# Bare_Arduino.net
KiCad netlist of a schematic drawn in EAGLE
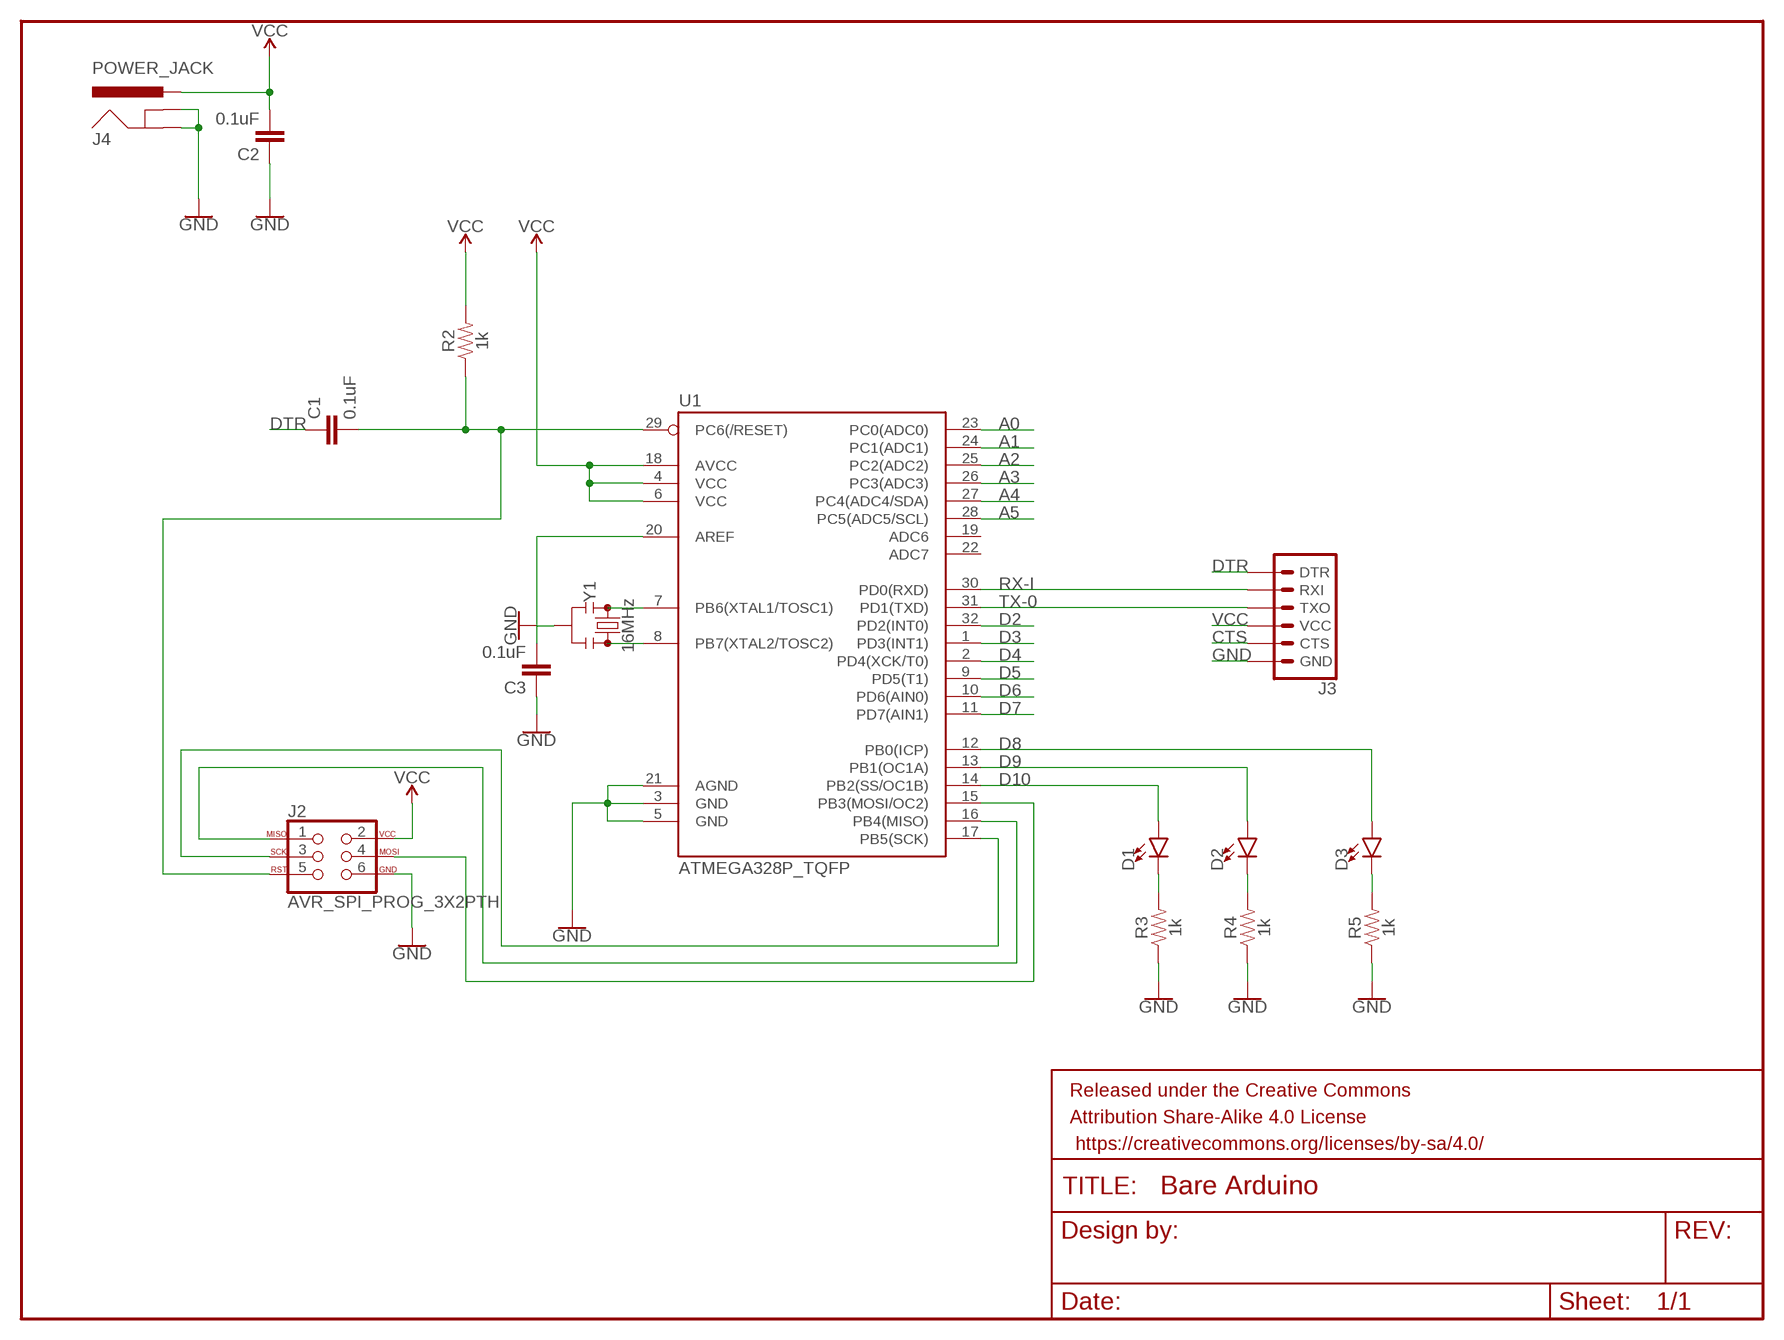
[diagram p0: schematic, sheet 1]

(export (version "E")
  (design (tool "Eeschema 10.0.6"))
  (components
    (comp (ref "C1")
      (value "0.1uF")
      (footprint "eagle-import:CAP-PTH-SMALL-KIT")
      (libsource (lib "eagle-import") (part "0.1UF-KIT-EZ-50V-20%"))
    )
    (comp (ref "C2")
      (value "0.1uF")
      (footprint "eagle-import:CAP-PTH-SMALL-KIT")
      (libsource (lib "eagle-import") (part "0.1UF-KIT-EZ-50V-20%"))
    )
    (comp (ref "C3")
      (value "0.1uF")
      (footprint "eagle-import:CAP-PTH-SMALL-KIT")
      (libsource (lib "eagle-import") (part "0.1UF-KIT-EZ-50V-20%"))
    )
    (comp (ref "D1")
      (value "LED5MM")
      (footprint "eagle-import:LED_5MM")
      (libsource (lib "eagle-import") (part "LED5MM"))
    )
    (comp (ref "D2")
      (value "LED5MM")
      (footprint "eagle-import:LED_5MM")
      (libsource (lib "eagle-import") (part "LED5MM"))
    )
    (comp (ref "D3")
      (value "LED5MM")
      (footprint "eagle-import:LED_5MM")
      (libsource (lib "eagle-import") (part "LED5MM"))
    )
    (comp (ref "FRAME1")
      (value "FRAME-LETTER")
      (footprint "eagle-import:CREATIVE_COMMONS")
      (libsource (lib "eagle-import") (part "FRAME-LETTER"))
    )
    (comp (ref "J2")
      (value "AVR_SPI_PROG_3X2PTH")
      (footprint "eagle-import:2X3")
      (libsource (lib "eagle-import") (part "AVR_SPI_PROG_3X2PTH"))
    )
    (comp (ref "J3")
      (value "6_PIN_SERIAL_TARGET")
      (footprint "eagle-import:1X06")
      (libsource (lib "eagle-import") (part "6_PIN_SERIAL_TARGET"))
    )
    (comp (ref "J4")
      (value "POWER_JACK")
      (footprint "eagle-import:POWER_JACK_PTH")
      (libsource (lib "eagle-import") (part "POWER_JACK"))
    )
    (comp (ref "R2")
      (value "1k")
      (footprint "eagle-import:AXIAL-0.3-KIT")
      (libsource (lib "eagle-import") (part "RESISTORAXIAL-0.3-KIT"))
    )
    (comp (ref "R3")
      (value "1k")
      (footprint "eagle-import:AXIAL-0.3-KIT")
      (libsource (lib "eagle-import") (part "RESISTORAXIAL-0.3-KIT"))
    )
    (comp (ref "R4")
      (value "1k")
      (footprint "eagle-import:AXIAL-0.3-KIT")
      (libsource (lib "eagle-import") (part "RESISTORAXIAL-0.3-KIT"))
    )
    (comp (ref "R5")
      (value "1k")
      (footprint "eagle-import:AXIAL-0.3-KIT")
      (libsource (lib "eagle-import") (part "RESISTORAXIAL-0.3-KIT"))
    )
    (comp (ref "U1")
      (value "ATMEGA328P_TQFP")
      (footprint "eagle-import:TQFP32-08")
      (libsource (lib "eagle-import") (part "ATMEGA328P_TQFP"))
    )
    (comp (ref "Y1")
      (value "16MHz")
      (footprint "eagle-import:RESONATOR-SMD-3.2X1.3")
      (libsource (lib "eagle-import") (part "RESONATOR-16MHZSMD_3.2X1.3"))
    )
  )
  (nets
    (net (code "1") (name "/A0") (class "Default")
      (node (ref "U1") (pin "23") (pinfunction "PC0(ADC0)_23") (pintype "bidirectional"))
    )
    (net (code "2") (name "/A1") (class "Default")
      (node (ref "U1") (pin "24") (pinfunction "PC1(ADC1)_24") (pintype "bidirectional"))
    )
    (net (code "3") (name "/A2") (class "Default")
      (node (ref "U1") (pin "25") (pinfunction "PC2(ADC2)_25") (pintype "bidirectional"))
    )
    (net (code "4") (name "/A3") (class "Default")
      (node (ref "U1") (pin "26") (pinfunction "PC3(ADC3)_26") (pintype "bidirectional"))
    )
    (net (code "5") (name "/A4") (class "Default")
      (node (ref "U1") (pin "27") (pinfunction "PC4(ADC4/SDA)_27") (pintype "bidirectional"))
    )
    (net (code "6") (name "/A5") (class "Default")
      (node (ref "U1") (pin "28") (pinfunction "PC5(ADC5/SCL)_28") (pintype "bidirectional"))
    )
    (net (code "7") (name "/CTS") (class "Default")
      (node (ref "J3") (pin "5") (pinfunction "CTS_5") (pintype "passive"))
    )
    (net (code "8") (name "/D2") (class "Default")
      (node (ref "U1") (pin "32") (pinfunction "PD2(INT0)_32") (pintype "bidirectional"))
    )
    (net (code "9") (name "/D3") (class "Default")
      (node (ref "U1") (pin "1") (pinfunction "PD3(INT1)_1") (pintype "bidirectional"))
    )
    (net (code "10") (name "/D4") (class "Default")
      (node (ref "U1") (pin "2") (pinfunction "PD4(XCK/T0)_2") (pintype "bidirectional"))
    )
    (net (code "11") (name "/D5") (class "Default")
      (node (ref "U1") (pin "9") (pinfunction "PD5(T1)_9") (pintype "bidirectional"))
    )
    (net (code "12") (name "/D6") (class "Default")
      (node (ref "U1") (pin "10") (pinfunction "PD6(AIN0)_10") (pintype "bidirectional"))
    )
    (net (code "13") (name "/D7") (class "Default")
      (node (ref "U1") (pin "11") (pinfunction "PD7(AIN1)_11") (pintype "bidirectional"))
    )
    (net (code "14") (name "/D8") (class "Default")
      (node (ref "D3") (pin "A") (pinfunction "A_A") (pintype "passive"))
      (node (ref "U1") (pin "12") (pinfunction "PB0(ICP)_12") (pintype "bidirectional"))
    )
    (net (code "15") (name "/D9") (class "Default")
      (node (ref "D2") (pin "A") (pinfunction "A_A") (pintype "passive"))
      (node (ref "U1") (pin "13") (pinfunction "PB1(OC1A)_13") (pintype "bidirectional"))
    )
    (net (code "16") (name "/D10") (class "Default")
      (node (ref "D1") (pin "A") (pinfunction "A_A") (pintype "passive"))
      (node (ref "U1") (pin "14") (pinfunction "PB2(SS/OC1B)_14") (pintype "bidirectional"))
    )
    (net (code "17") (name "/DTR") (class "Default")
      (node (ref "C1") (pin "1") (pinfunction "1_1") (pintype "passive"))
      (node (ref "J3") (pin "1") (pinfunction "DTR_1") (pintype "passive"))
    )
    (net (code "18") (name "/RX-I") (class "Default")
      (node (ref "J3") (pin "2") (pinfunction "RXI_2") (pintype "passive"))
      (node (ref "U1") (pin "30") (pinfunction "PD0(RXD)_30") (pintype "bidirectional"))
    )
    (net (code "19") (name "/TX-0") (class "Default")
      (node (ref "J3") (pin "3") (pinfunction "TXO_3") (pintype "passive"))
      (node (ref "U1") (pin "31") (pinfunction "PD1(TXD)_31") (pintype "bidirectional"))
    )
    (net (code "20") (name "GND") (class "Default")
      (node (ref "C2") (pin "1") (pinfunction "1_1") (pintype "passive"))
      (node (ref "C3") (pin "1") (pinfunction "1_1") (pintype "passive"))
      (node (ref "J2") (pin "6") (pinfunction "6_6") (pintype "passive"))
      (node (ref "J3") (pin "6") (pinfunction "GND_6") (pintype "passive"))
      (node (ref "J4") (pin "GND") (pinfunction "GND_GND") (pintype "bidirectional"))
      (node (ref "J4") (pin "GNDBREAK") (pinfunction "GNDBREAK_GNDBREAK") (pintype "bidirectional"))
      (node (ref "R3") (pin "P$1") (pinfunction "1_P$1") (pintype "passive"))
      (node (ref "R4") (pin "P$1") (pinfunction "1_P$1") (pintype "passive"))
      (node (ref "R5") (pin "P$1") (pinfunction "1_P$1") (pintype "passive"))
      (node (ref "U1") (pin "21") (pinfunction "AGND_21") (pintype "bidirectional"))
      (node (ref "U1") (pin "3") (pinfunction "GND_3") (pintype "bidirectional"))
      (node (ref "U1") (pin "5") (pinfunction "GND_5") (pintype "bidirectional"))
      (node (ref "Y1") (pin "2") (pinfunction "2_2") (pintype "passive"))
    )
    (net (code "21") (name "Net-(D1-C)") (class "Default")
      (node (ref "D1") (pin "K") (pinfunction "C_K") (pintype "passive"))
      (node (ref "R3") (pin "P$2") (pinfunction "2_P$2") (pintype "passive"))
    )
    (net (code "22") (name "Net-(D2-C)") (class "Default")
      (node (ref "D2") (pin "K") (pinfunction "C_K") (pintype "passive"))
      (node (ref "R4") (pin "P$2") (pinfunction "2_P$2") (pintype "passive"))
    )
    (net (code "23") (name "Net-(D3-C)") (class "Default")
      (node (ref "D3") (pin "K") (pinfunction "C_K") (pintype "passive"))
      (node (ref "R5") (pin "P$2") (pinfunction "2_P$2") (pintype "passive"))
    )
    (net (code "24") (name "Net-(R2-1)") (class "Default")
      (node (ref "C1") (pin "2") (pinfunction "2_2") (pintype "passive"))
      (node (ref "J2") (pin "5") (pinfunction "5_5") (pintype "passive"))
      (node (ref "R2") (pin "P$1") (pinfunction "1_P$1") (pintype "passive"))
      (node (ref "U1") (pin "29") (pinfunction "PC6(/RESET)_29") (pintype "bidirectional"))
    )
    (net (code "25") (name "Net-(U1-AREF)") (class "Default")
      (node (ref "C3") (pin "2") (pinfunction "2_2") (pintype "passive"))
      (node (ref "U1") (pin "20") (pinfunction "AREF_20") (pintype "bidirectional"))
    )
    (net (code "26") (name "Net-(U1-PB3(MOSI{slash}OC2))") (class "Default")
      (node (ref "J2") (pin "4") (pinfunction "4_4") (pintype "passive"))
      (node (ref "U1") (pin "15") (pinfunction "PB3(MOSI/OC2)_15") (pintype "bidirectional"))
    )
    (net (code "27") (name "Net-(U1-PB4(MISO))") (class "Default")
      (node (ref "J2") (pin "1") (pinfunction "1_1") (pintype "passive"))
      (node (ref "U1") (pin "16") (pinfunction "PB4(MISO)_16") (pintype "bidirectional"))
    )
    (net (code "28") (name "Net-(U1-PB5(SCK))") (class "Default")
      (node (ref "J2") (pin "3") (pinfunction "3_3") (pintype "passive"))
      (node (ref "U1") (pin "17") (pinfunction "PB5(SCK)_17") (pintype "bidirectional"))
    )
    (net (code "29") (name "Net-(U1-PB6(XTAL1{slash}TOSC1))") (class "Default")
      (node (ref "U1") (pin "7") (pinfunction "PB6(XTAL1/TOSC1)_7") (pintype "bidirectional"))
      (node (ref "Y1") (pin "1") (pinfunction "1_1") (pintype "passive"))
    )
    (net (code "30") (name "Net-(U1-PB7(XTAL2{slash}TOSC2))") (class "Default")
      (node (ref "U1") (pin "8") (pinfunction "PB7(XTAL2/TOSC2)_8") (pintype "bidirectional"))
      (node (ref "Y1") (pin "3") (pinfunction "3_3") (pintype "passive"))
    )
    (net (code "31") (name "VCC") (class "Default")
      (node (ref "C2") (pin "2") (pinfunction "2_2") (pintype "passive"))
      (node (ref "J2") (pin "2") (pinfunction "2_2") (pintype "passive"))
      (node (ref "J3") (pin "4") (pinfunction "VCC_4") (pintype "passive"))
      (node (ref "J4") (pin "PWR") (pinfunction "PWR_PWR") (pintype "bidirectional"))
      (node (ref "R2") (pin "P$2") (pinfunction "2_P$2") (pintype "passive"))
      (node (ref "U1") (pin "18") (pinfunction "AVCC_18") (pintype "bidirectional"))
      (node (ref "U1") (pin "4") (pinfunction "VCC_4") (pintype "bidirectional"))
      (node (ref "U1") (pin "6") (pinfunction "VCC_6") (pintype "bidirectional"))
    )
    (net (code "32") (name "unconnected-(U1-ADC6-Pad19)") (class "Default")
      (node (ref "U1") (pin "19") (pinfunction "ADC6_19") (pintype "bidirectional"))
    )
    (net (code "33") (name "unconnected-(U1-ADC7-Pad22)") (class "Default")
      (node (ref "U1") (pin "22") (pinfunction "ADC7_22") (pintype "bidirectional"))
    )
  )
)
